# Voltage_Regulator.net
KiCad netlist of a schematic drawn in Altium Designer
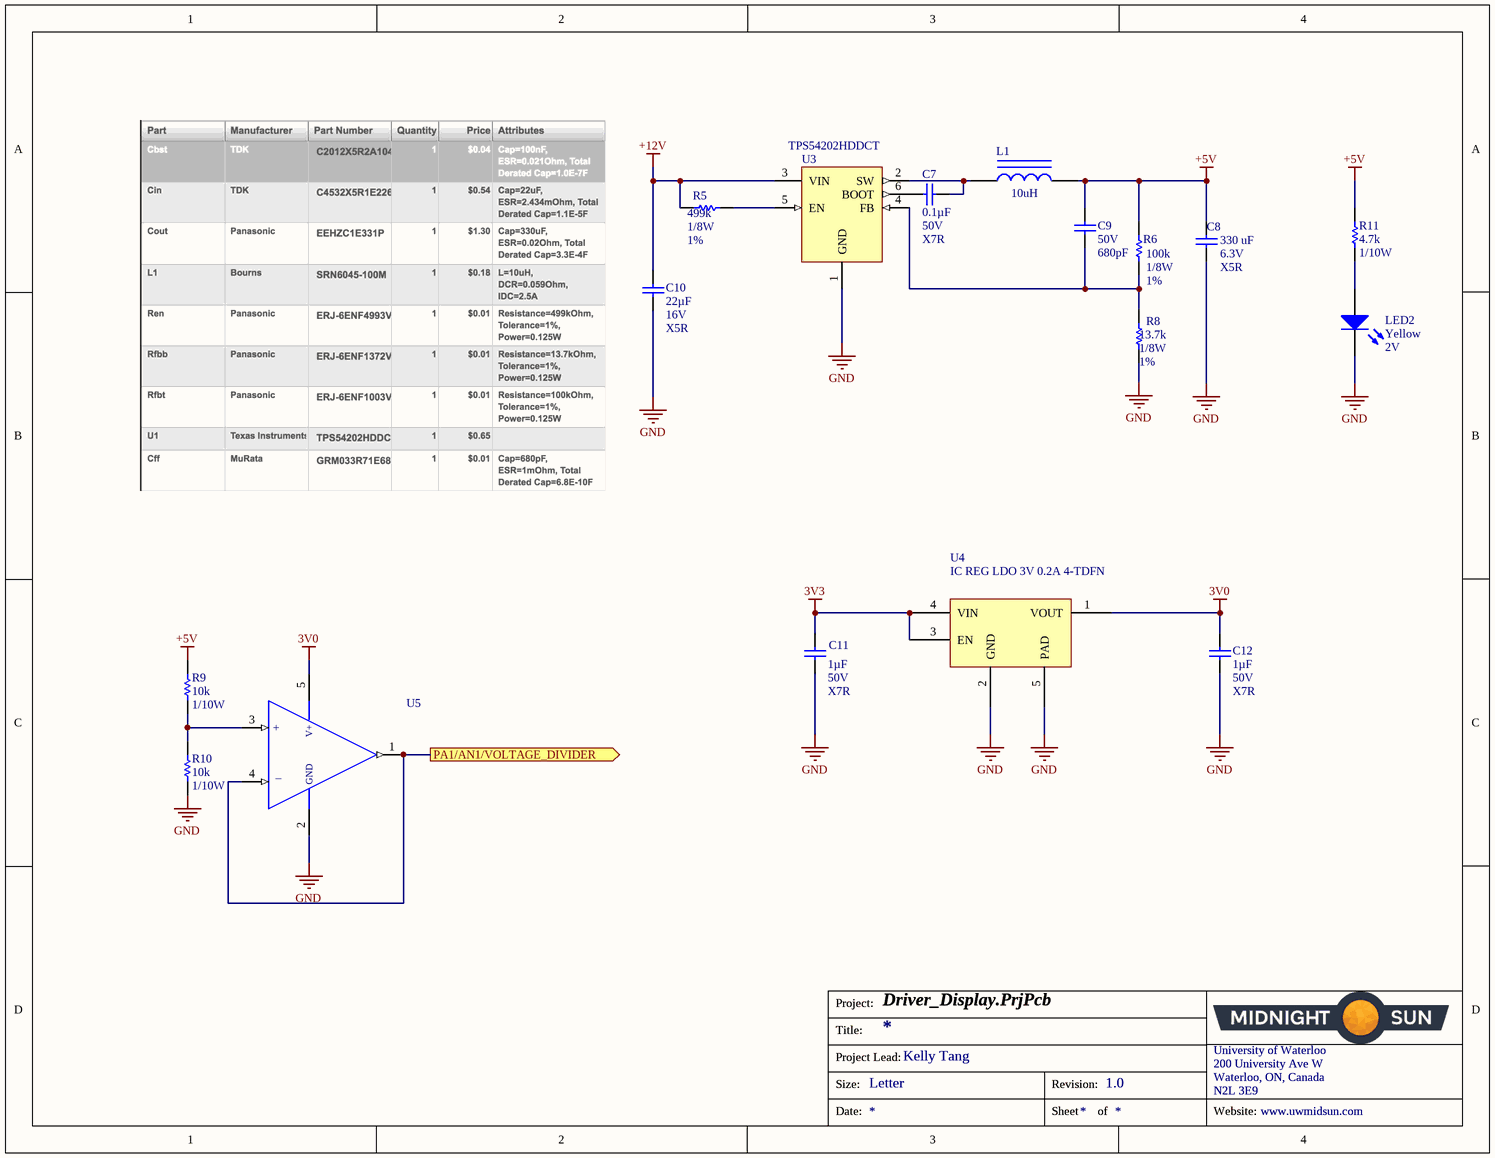
[diagram p0: Voltage Regulator.SchDoc]

(export (version "E")
  (design (tool "Eeschema 10.0.6"))
  (components
    (comp (ref "C7")
      (value "CAP CER 0.1UF 50V 10% X7R 0603")
      (footprint "CAP, 0603")
      (description "0.10µF ±10% 50V Ceramic Capacitor X7R 0603 (1608 Metric)")
      (fields
        (field (name "TOLERANCE") "±10%")
        (field (name "CAPACITANCE") "0.1µF")
        (field (name "VOLTAGE") "50V")
        (field (name "TEMPERATURE COEFFICIENT") "X7R")
      )
      (libsource (lib "Schematic Diagrams") (part "CAP CER 0.1UF 50V 10% X7R 0603"))
    )
    (comp (ref "C8")
      (value "CAP CER 330UF 6.3V X5R 1210")
      (footprint "CAP, 1210")
      (description "330µF ±20% 6.3V Ceramic Capacitor X5R 1210 (3225 Metric)")
      (fields
        (field (name "MANUFACTURER") "Taiyo Yuden")
        (field (name "MANUFACTURER PART NUMBER") "JMK325ABJ337MM-P")
        (field (name "CAPACITANCE") "330 uF")
        (field (name "VOLTAGE") "6.3V")
        (field (name "TEMPERATURE COEFFICIENT") "X5R")
      )
      (libsource (lib "Schematic Diagrams") (part "CAP CER 330UF 6.3V X5R 1210"))
    )
    (comp (ref "C9")
      (value "CAP CER 680PF 50V C0G/NP0 0603")
      (footprint "CAP, 0603")
      (description "680pF ±5% 50V Ceramic Capacitor C0G, NP0 0603 (1608 Metric)")
      (fields
        (field (name "MANUFACTURER") "Samsung")
        (field (name "MANUFACTURER PART NUMBER") "CL10C681JB8NNNC")
        (field (name "VOLTAGE") "50V")
        (field (name "CAPACITANCE") "680pF")
      )
      (libsource (lib "Schematic Diagrams") (part "CAP CER 680PF 50V C0G 0603"))
    )
    (comp (ref "C10")
      (value "CAP CER 22UF 16V ±20% X5R 1210")
      (footprint "CAP, 1210")
      (description "22µF ±20% 16V Ceramic Capacitor X5R 1210 (3225 Metric)")
      (fields
        (field (name "TOLERANCE") "±20%")
        (field (name "CAPACITANCE") "22µF")
        (field (name "VOLTAGE") "16V")
        (field (name "TEMPERATURE COEFFICIENT") "X5R")
      )
      (libsource (lib "Schematic Diagrams") (part "CAP CER 22UF 16V ±20% X5R 1210"))
    )
    (comp (ref "C11")
      (value "CAP CER 1UF 50V 10% X7R 0603")
      (footprint "CAP, 0603")
      (description "1µF ±10% 50V Ceramic Capacitor X7R 0603 (1608 Metric)")
      (fields
        (field (name "TOLERANCE") "±10%")
        (field (name "CAPACITANCE") "1µF")
        (field (name "VOLTAGE") "50V")
        (field (name "TEMPERATURE COEFFICIENT") "X7R")
      )
      (libsource (lib "Schematic Diagrams") (part "CAP CER 1UF 50V 10% X7R 0603"))
    )
    (comp (ref "C12")
      (value "CAP CER 1UF 50V 10% X7R 0603")
      (footprint "CAP, 0603")
      (description "1µF ±10% 50V Ceramic Capacitor X7R 0603 (1608 Metric)")
      (fields
        (field (name "TOLERANCE") "±10%")
        (field (name "CAPACITANCE") "1µF")
        (field (name "VOLTAGE") "50V")
        (field (name "TEMPERATURE COEFFICIENT") "X7R")
      )
      (libsource (lib "Schematic Diagrams") (part "CAP CER 1UF 50V 10% X7R 0603"))
    )
    (comp (ref "L1")
      (value "IND 10UH 2.8A 59 MOHM SMD")
      (footprint "INDP100102X31N")
      (description "10µH Shielded Inductor 2.8A 59 mOhm Max Nonstandard")
      (fields
        (field (name "MANUFACTURER") "Sumida")
        (field (name "MANUFACTURER PART NUMBER") "CDRH103RNP-100NC-B")
        (field (name "INDUCTANCE") "10uH")
      )
      (libsource (lib "Schematic Diagrams") (part "IND 10UH 2.8A 59 MOHM SMD"))
    )
    (comp (ref "LED2")
      (value "LED YELLOW CLEAR 2.1V 0603")
      (footprint "LED_0603")
      (description "Yellow 590nm LED Indication - Discrete 2V 0603 (1608 Metric)")
      (fields
        (field (name "MANUFACTURER") "Wurth Electronics Inc.")
        (field (name "MANUFACTURER PART NUMBER") "150060YS75000")
        (field (name "COLOR") "Yellow")
        (field (name "VOLTAGE - FORWARD (VF) (TYP)") "2V")
      )
      (libsource (lib "Schematic Diagrams") (part "LED YELLOW CLEAR 2.1V 0603"))
    )
    (comp (ref "R5")
      (value "RES 499K OHM 1% 1/4W 1206")
      (footprint "RES 1206")
      (fields
        (field (name "MANUFACTURER") "Stackpole Electronics")
        (field (name "MANUFACTURER PART NUMBER") "RMCF1206FT499K")
        (field (name "RESISTANCE") "499k")
        (field (name "TOLERANCE") "1%")
        (field (name "MAX POWER DISSIPATION") "1/8W")
      )
      (libsource (lib "Schematic Diagrams") (part "RES 499K OHM 1% 1/4W 1206"))
    )
    (comp (ref "R6")
      (value "ES 100K OHM 1% 1/4W 1206")
      (footprint "RES 1206")
      (description "100 kOhms ±1% 0.25W, 1/4W Chip Resistor 1206 (3216 Metric) Moisture Resistant Thick Film")
      (fields
        (field (name "MANUFACTURER") "Yageo")
        (field (name "MANUFACTURER PART NUMBER") "RC1206FR-07100KL")
        (field (name "TOLERANCE") "1%")
        (field (name "RESISTANCE") "100k")
        (field (name "POWER RATING") "1/8W")
      )
      (libsource (lib "Schematic Diagrams") (part "RES 100K OHM 1% 1/4W 1206"))
    )
    (comp (ref "R8")
      (value "RES 13.7K OHM 1% 1/4W 1206")
      (footprint "RES 1206")
      (description "13.7 kOhms ±1% 0.25W, 1/4W Chip Resistor 1206 (3216 Metric) Moisture Resistant Thick Film")
      (fields
        (field (name "MANUFACTURER") "Yageo")
        (field (name "MANUFACTURER PART NUMBER") "RC1206FR-0713K7L")
        (field (name "RESISTANCE") "13.7k")
        (field (name "TOLERANCE") "1%")
        (field (name "POWER RATING") "1/8W")
      )
      (libsource (lib "Schematic Diagrams") (part "RES 13.7K OHM 1% 1/4W 1206"))
    )
    (comp (ref "R9")
      (value "RES 10K OHM 1% 1/10W 0603")
      (footprint "RES, 0603")
      (description "RES SMD 10K OHM 1% 1/10W 0603")
      (fields
        (field (name "TOLERANCE") "±1%")
        (field (name "RESISTANCE") "10k")
        (field (name "POWER") "1/10W")
      )
      (libsource (lib "Schematic Diagrams") (part "RES 10K OHM 1% 1/10W 0603"))
    )
    (comp (ref "R10")
      (value "RES 10K OHM 1% 1/10W 0603")
      (footprint "RES, 0603")
      (description "RES SMD 10K OHM 1% 1/10W 0603")
      (fields
        (field (name "TOLERANCE") "±1%")
        (field (name "RESISTANCE") "10k")
        (field (name "POWER") "1/10W")
      )
      (libsource (lib "Schematic Diagrams") (part "RES 10K OHM 1% 1/10W 0603"))
    )
    (comp (ref "R11")
      (value "RES 4.7K OHM 1% 1/10W 0603")
      (footprint "RES, 0603")
      (description "4.7k Ohm ±1% 0.1W, 1/10W Chip Resistor 0603 (1608 Metric) Moisture Resistant Thick Film")
      (fields
        (field (name "TOLERANCE") "±1%")
        (field (name "RESISTANCE (OHMS)") "4.7k")
        (field (name "POWER (WATTS)") "1/10W")
      )
      (libsource (lib "Schematic Diagrams") (part "RES 4.7K OHM 1% 1/10W 0603"))
    )
    (comp (ref "U3")
      (value "IC REG BUCK ADJ 2A SYNC 6SOT")
      (footprint "SOT23-6")
      (description "Buck Switching Regulator IC Positive Adjustable 0.596V 1 Output 2A SOT-23-6 Thin, TSOT-23-6")
      (fields
        (field (name "MANUFACTURER") "Texas Instruments")
        (field (name "MANUFACTURER PART NUMBER") "TPS54202HDDCT")
      )
      (libsource (lib "Schematic Diagrams") (part "IC REG BUCK ADJ 2A SYNC 6SOT"))
    )
    (comp (ref "U4")
      (value "IC REG LDO 3V 0.2A 4-TDFN")
      (footprint "IC REG LDO 3V 0.2A 4-TDFN")
      (fields
        (field (name "MANUFACTURER") "Microchip Technology")
        (field (name "MANUFACTURER PART NUMBER") "MIC94310-PYMT-TR")
      )
      (libsource (lib "Schematic Diagrams") (part "IC REG LDO 3V 0.2A 4-TDFN"))
    )
    (comp (ref "U5")
      (value "IC OP AMP GEN PURPOSE RR 10MHZ SOT-23-5")
      (footprint "IC OP AMP GP RR 10MHZ SOT-23-5")
      (description "General Purpose Amplifier 1 Circuit Rail-to-Rail SOT-23-5")
      (libsource (lib "Schematic Diagrams") (part "IC OP AMP GEN PURPOSE RR 10MHZ SOT-23-5"))
    )
  )
  (nets
    (net (code "1") (name "+5V") (class "Default")
      (node (ref "C8") (pin "1") (pinfunction "1_1") (pintype "passive"))
      (node (ref "C9") (pin "1") (pinfunction "1_1") (pintype "passive"))
      (node (ref "L1") (pin "2") (pinfunction "2_2") (pintype "passive"))
      (node (ref "R11") (pin "1") (pinfunction "1_1") (pintype "passive"))
      (node (ref "R6") (pin "1") (pinfunction "1_1") (pintype "passive"))
      (node (ref "R9") (pin "1") (pinfunction "1_1") (pintype "passive"))
    )
    (net (code "2") (name "+12V") (class "Default")
      (node (ref "C10") (pin "1") (pinfunction "1_1") (pintype "passive"))
      (node (ref "R5") (pin "2") (pinfunction "2_2") (pintype "passive"))
      (node (ref "U3") (pin "3") (pinfunction "VIN_3") (pintype "power_in"))
    )
    (net (code "3") (name "/PA1{slash}AN1{slash}VOLTAGE_DIVIDER") (class "Default")
      (node (ref "U5") (pin "1") (pinfunction "OUTPUT_1") (pintype "output"))
      (node (ref "U5") (pin "4") (pinfunction "-IN_4") (pintype "input"))
    )
    (net (code "4") (name "3V0") (class "Default")
      (node (ref "C12") (pin "1") (pinfunction "1_1") (pintype "passive"))
      (node (ref "U4") (pin "1") (pinfunction "VOUT_1") (pintype "passive"))
      (node (ref "U5") (pin "5") (pinfunction "VDD_5") (pintype "power_in"))
    )
    (net (code "5") (name "3V3") (class "Default")
      (node (ref "C11") (pin "1") (pinfunction "1_1") (pintype "passive"))
      (node (ref "U4") (pin "3") (pinfunction "EN_3") (pintype "passive"))
      (node (ref "U4") (pin "4") (pinfunction "VIN_4") (pintype "passive"))
    )
    (net (code "6") (name "GND") (class "Default")
      (node (ref "C10") (pin "2") (pinfunction "2_2") (pintype "passive"))
      (node (ref "C11") (pin "2") (pinfunction "2_2") (pintype "passive"))
      (node (ref "C12") (pin "2") (pinfunction "2_2") (pintype "passive"))
      (node (ref "C8") (pin "2") (pinfunction "2_2") (pintype "passive"))
      (node (ref "LED2") (pin "2") (pinfunction "K_2") (pintype "passive"))
      (node (ref "R10") (pin "2") (pinfunction "2_2") (pintype "passive"))
      (node (ref "R8") (pin "2") (pinfunction "2_2") (pintype "passive"))
      (node (ref "U3") (pin "1") (pinfunction "GND_1") (pintype "power_in"))
      (node (ref "U4") (pin "2") (pinfunction "GND_2") (pintype "passive"))
      (node (ref "U4") (pin "5") (pinfunction "PAD_5") (pintype "passive"))
      (node (ref "U5") (pin "2") (pinfunction "VSS_2") (pintype "power_in"))
    )
    (net (code "7") (name "Net-(LED2-A)") (class "Default")
      (node (ref "LED2") (pin "1") (pinfunction "A_1") (pintype "passive"))
      (node (ref "R11") (pin "2") (pinfunction "2_2") (pintype "passive"))
    )
    (net (code "8") (name "Net-(U3-BOOT)") (class "Default")
      (node (ref "C7") (pin "1") (pinfunction "1_1") (pintype "passive"))
      (node (ref "U3") (pin "6") (pinfunction "BOOT_6") (pintype "output"))
    )
    (net (code "9") (name "Net-(U3-EN)") (class "Default")
      (node (ref "R5") (pin "1") (pinfunction "1_1") (pintype "passive"))
      (node (ref "U3") (pin "5") (pinfunction "EN_5") (pintype "input"))
    )
    (net (code "10") (name "Net-(U3-FB)") (class "Default")
      (node (ref "C9") (pin "2") (pinfunction "2_2") (pintype "passive"))
      (node (ref "R6") (pin "2") (pinfunction "2_2") (pintype "passive"))
      (node (ref "R8") (pin "1") (pinfunction "1_1") (pintype "passive"))
      (node (ref "U3") (pin "4") (pinfunction "FB_4") (pintype "input"))
    )
    (net (code "11") (name "Net-(U3-SW)") (class "Default")
      (node (ref "C7") (pin "2") (pinfunction "2_2") (pintype "passive"))
      (node (ref "L1") (pin "1") (pinfunction "1_1") (pintype "passive"))
      (node (ref "U3") (pin "2") (pinfunction "SW_2") (pintype "output"))
    )
    (net (code "12") (name "Net-(U5-+IN)") (class "Default")
      (node (ref "R10") (pin "1") (pinfunction "1_1") (pintype "passive"))
      (node (ref "R9") (pin "2") (pinfunction "2_2") (pintype "passive"))
      (node (ref "U5") (pin "3") (pinfunction "+IN_3") (pintype "input"))
    )
  )
)
